# Display.net
KiCad netlist of a schematic drawn in Altium Designer
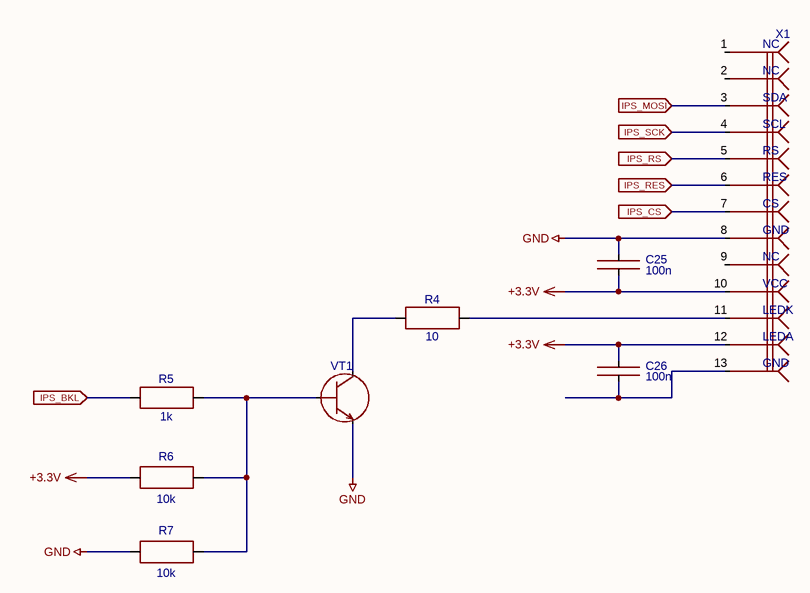
[diagram p0: Display.SchDoc]

(export (version "E")
  (design (tool "Eeschema 10.0.6"))
  (components
    (comp (ref "C25")
      (value "100n")
      (footprint "CAPC1608X09N")
      (description "GRM188R71E104KA01D")
      (libsource (lib "Capasitors") (part "C0603-100n-25V-X7R-10%"))
    )
    (comp (ref "C26")
      (value "100n")
      (footprint "CAPC1608X09N")
      (description "GRM188R71E104KA01D")
      (libsource (lib "Capasitors") (part "C0603-100n-25V-X7R-10%"))
    )
    (comp (ref "R4")
      (value "10")
      (footprint "RESC2012X05N")
      (libsource (lib "Resistors") (part "R-0805-10-5%"))
    )
    (comp (ref "R5")
      (value "1k")
      (footprint "RESC1608X05N")
      (libsource (lib "Resistors") (part "R-0603-1k-5%"))
    )
    (comp (ref "R6")
      (value "10k")
      (footprint "RESC2012X05N")
      (libsource (lib "Resistors") (part "R-0805-10k-5%"))
    )
    (comp (ref "R7")
      (value "10k")
      (footprint "RESC2012X05N")
      (libsource (lib "Resistors") (part "R-0805-10k-5%"))
    )
    (comp (ref "VT1")
      (value "BC817")
      (footprint "SOT23127P600-8N")
      (description "Транзистор NPN 45В 0.5А 0.31Вт")
      (libsource (lib "Transistors") (part "BC817-16LT1G"))
    )
    (comp (ref "X1") (value "IPC-1.14") (footprint "144-IPS") (libsource (lib "Displays") (part "IPC-1.14")))
  )
  (nets
    (net (code "1") (name "+3.3V") (class "Default")
      (node (ref "C25") (pin "1") (pinfunction "1_1") (pintype "passive"))
      (node (ref "C26") (pin "2") (pinfunction "2_2") (pintype "passive"))
      (node (ref "R6") (pin "2") (pinfunction "2_2") (pintype "passive"))
      (node (ref "X1") (pin "10") (pinfunction "SHIELD_10") (pintype "passive"))
      (node (ref "X1") (pin "12") (pinfunction "SHIELD_12") (pintype "passive"))
    )
    (net (code "2") (name "/IPS_BKL") (class "Default")
      (node (ref "R5") (pin "1") (pinfunction "1_1") (pintype "passive"))
    )
    (net (code "3") (name "/IPS_CS") (class "Default")
      (node (ref "X1") (pin "7") (pinfunction "SHIELD_7") (pintype "passive"))
    )
    (net (code "4") (name "/IPS_MOSI") (class "Default")
      (node (ref "X1") (pin "3") (pinfunction "D+_3") (pintype "passive"))
    )
    (net (code "5") (name "/IPS_RES") (class "Default")
      (node (ref "X1") (pin "6") (pinfunction "SHIELD_6") (pintype "passive"))
    )
    (net (code "6") (name "/IPS_RS") (class "Default")
      (node (ref "X1") (pin "5") (pinfunction "GND_5") (pintype "passive"))
    )
    (net (code "7") (name "/IPS_SCK") (class "Default")
      (node (ref "X1") (pin "4") (pinfunction "ID_4") (pintype "passive"))
    )
    (net (code "8") (name "GND") (class "Default")
      (node (ref "C25") (pin "2") (pinfunction "2_2") (pintype "passive"))
      (node (ref "R7") (pin "2") (pinfunction "2_2") (pintype "passive"))
      (node (ref "VT1") (pin "E") (pinfunction "E_E") (pintype "passive"))
      (node (ref "X1") (pin "8") (pinfunction "SHIELD_8") (pintype "passive"))
    )
    (net (code "9") (name "Net-(C26-Pad1)") (class "Default")
      (node (ref "C26") (pin "1") (pinfunction "1_1") (pintype "passive"))
      (node (ref "X1") (pin "13") (pinfunction "SHIELD_13") (pintype "passive"))
    )
    (net (code "10") (name "Net-(R4-Pad1)") (class "Default")
      (node (ref "R4") (pin "1") (pinfunction "1_1") (pintype "passive"))
      (node (ref "VT1") (pin "C") (pinfunction "C_C") (pintype "passive"))
    )
    (net (code "11") (name "Net-(R4-Pad2)") (class "Default")
      (node (ref "R4") (pin "2") (pinfunction "2_2") (pintype "passive"))
      (node (ref "X1") (pin "11") (pinfunction "SHIELD_11") (pintype "passive"))
    )
    (net (code "12") (name "Net-(R5-Pad2)") (class "Default")
      (node (ref "R5") (pin "2") (pinfunction "2_2") (pintype "passive"))
      (node (ref "R6") (pin "1") (pinfunction "1_1") (pintype "passive"))
      (node (ref "R7") (pin "1") (pinfunction "1_1") (pintype "passive"))
      (node (ref "VT1") (pin "B") (pinfunction "B_B") (pintype "passive"))
    )
    (net (code "13") (name "unconnected-(X1-D--Pad2)") (class "Default")
      (node (ref "X1") (pin "2") (pinfunction "D-_2") (pintype "passive"))
    )
    (net (code "14") (name "unconnected-(X1-SHIELD-Pad9)") (class "Default")
      (node (ref "X1") (pin "9") (pinfunction "SHIELD_9") (pintype "passive"))
    )
    (net (code "15") (name "unconnected-(X1-VBUS-Pad1)") (class "Default")
      (node (ref "X1") (pin "1") (pinfunction "VBUS_1") (pintype "passive"))
    )
  )
)
